# main.net
KiCad netlist of a schematic drawn in EAGLE
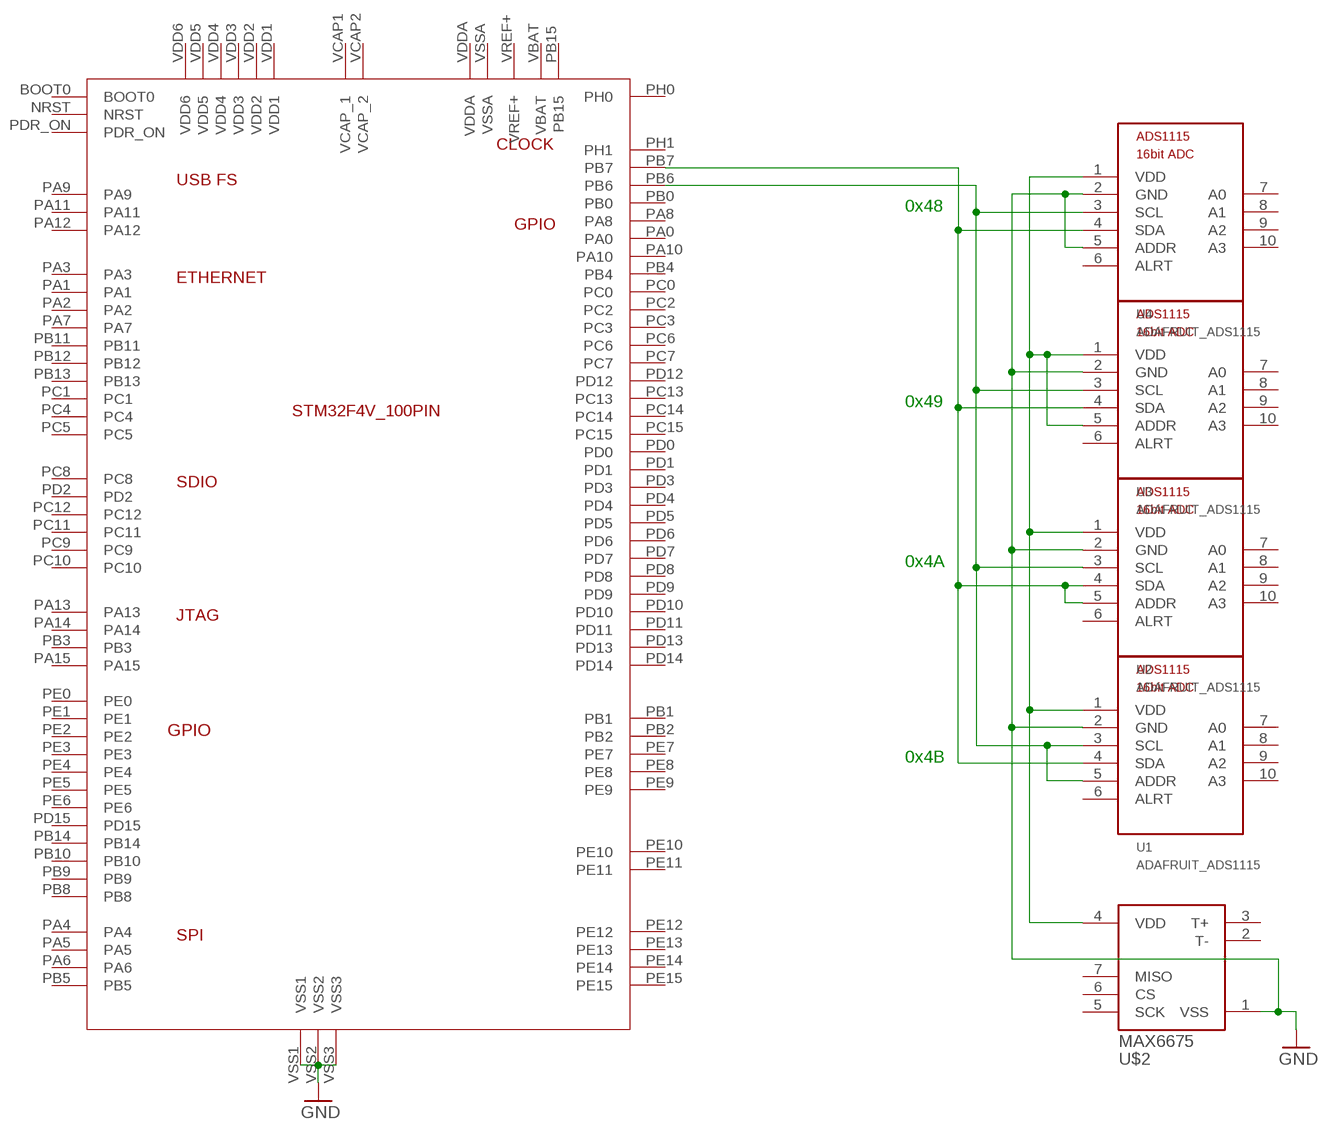
[diagram p0: schematic, sheet 1]

(export (version "E")
  (design (tool "Eeschema 10.0.6"))
  (components
    (comp (ref "U$1")
      (value "STM32F4V_100PIN_GPSBOARD")
      (footprint "eagle-import:LQFP100")
      (libsource (lib "eagle-import") (part "STM32F4V_100PIN_GPSBOARD"))
    )
    (comp (ref "U$2")
      (value "MAX6675")
      (footprint "eagle-import:SO08")
      (libsource (lib "eagle-import") (part "MAX6675"))
    )
    (comp (ref "U1")
      (value "ADAFRUIT_ADS1115")
      (footprint "eagle-import:ADAFRUIT_ADS1115_16BIT_I2C_ADC")
      (libsource (lib "eagle-import") (part "ADAFRUIT_ADS1115"))
    )
    (comp (ref "U2")
      (value "ADAFRUIT_ADS1115")
      (footprint "eagle-import:ADAFRUIT_ADS1115_16BIT_I2C_ADC")
      (libsource (lib "eagle-import") (part "ADAFRUIT_ADS1115"))
    )
    (comp (ref "U3")
      (value "ADAFRUIT_ADS1115")
      (footprint "eagle-import:ADAFRUIT_ADS1115_16BIT_I2C_ADC")
      (libsource (lib "eagle-import") (part "ADAFRUIT_ADS1115"))
    )
    (comp (ref "U4")
      (value "ADAFRUIT_ADS1115")
      (footprint "eagle-import:ADAFRUIT_ADS1115_16BIT_I2C_ADC")
      (libsource (lib "eagle-import") (part "ADAFRUIT_ADS1115"))
    )
  )
  (nets
    (net (code "1") (name "/VDD1") (class "Default")
      (node (ref "U$1") (pin "VDD1") (pinfunction "VDD1_VDD1") (pintype "power_in"))
    )
    (net (code "2") (name "/VDD2") (class "Default")
      (node (ref "U$1") (pin "VDD2") (pinfunction "VDD2_VDD2") (pintype "power_in"))
    )
    (net (code "3") (name "/VDD3") (class "Default")
      (node (ref "U$1") (pin "VDD3") (pinfunction "VDD3_VDD3") (pintype "power_in"))
    )
    (net (code "4") (name "/VDD4") (class "Default")
      (node (ref "U$1") (pin "VDD4") (pinfunction "VDD4_VDD4") (pintype "power_in"))
    )
    (net (code "5") (name "/VDD5") (class "Default")
      (node (ref "U$1") (pin "VDD5") (pinfunction "VDD5_VDD5") (pintype "power_in"))
    )
    (net (code "6") (name "/VDD6") (class "Default")
      (node (ref "U$1") (pin "VDD6") (pinfunction "VDD6_VDD6") (pintype "power_in"))
    )
    (net (code "7") (name "GND") (class "Default")
      (node (ref "U$1") (pin "VSS1") (pinfunction "VSS1_VSS1") (pintype "power_in"))
      (node (ref "U$1") (pin "VSS2") (pinfunction "VSS2_VSS2") (pintype "power_in"))
      (node (ref "U$1") (pin "VSS3") (pinfunction "VSS3_VSS3") (pintype "power_in"))
      (node (ref "U$2") (pin "1") (pinfunction "VSS_1") (pintype "bidirectional"))
      (node (ref "U1") (pin "2") (pinfunction "GND_2") (pintype "bidirectional"))
      (node (ref "U2") (pin "2") (pinfunction "GND_2") (pintype "bidirectional"))
      (node (ref "U3") (pin "2") (pinfunction "GND_2") (pintype "bidirectional"))
      (node (ref "U4") (pin "2") (pinfunction "GND_2") (pintype "bidirectional"))
      (node (ref "U4") (pin "5") (pinfunction "ADDR_5") (pintype "bidirectional"))
    )
    (net (code "8") (name "Net-(U$2-VDD)") (class "Default")
      (node (ref "U$2") (pin "4") (pinfunction "VDD_4") (pintype "bidirectional"))
      (node (ref "U1") (pin "1") (pinfunction "VDD_1") (pintype "bidirectional"))
      (node (ref "U2") (pin "1") (pinfunction "VDD_1") (pintype "bidirectional"))
      (node (ref "U3") (pin "1") (pinfunction "VDD_1") (pintype "bidirectional"))
      (node (ref "U3") (pin "5") (pinfunction "ADDR_5") (pintype "bidirectional"))
      (node (ref "U4") (pin "1") (pinfunction "VDD_1") (pintype "bidirectional"))
    )
    (net (code "9") (name "Net-(U1-ADDR)") (class "Default")
      (node (ref "U$1") (pin "PB6") (pinfunction "PB6_PB6") (pintype "bidirectional"))
      (node (ref "U1") (pin "3") (pinfunction "SCL_3") (pintype "bidirectional"))
      (node (ref "U1") (pin "5") (pinfunction "ADDR_5") (pintype "bidirectional"))
      (node (ref "U2") (pin "3") (pinfunction "SCL_3") (pintype "bidirectional"))
      (node (ref "U3") (pin "3") (pinfunction "SCL_3") (pintype "bidirectional"))
      (node (ref "U4") (pin "3") (pinfunction "SCL_3") (pintype "bidirectional"))
    )
    (net (code "10") (name "Net-(U1-SDA)") (class "Default")
      (node (ref "U$1") (pin "PB7") (pinfunction "PB7_PB7") (pintype "bidirectional"))
      (node (ref "U1") (pin "4") (pinfunction "SDA_4") (pintype "bidirectional"))
      (node (ref "U2") (pin "4") (pinfunction "SDA_4") (pintype "bidirectional"))
      (node (ref "U2") (pin "5") (pinfunction "ADDR_5") (pintype "bidirectional"))
      (node (ref "U3") (pin "4") (pinfunction "SDA_4") (pintype "bidirectional"))
      (node (ref "U4") (pin "4") (pinfunction "SDA_4") (pintype "bidirectional"))
    )
    (net (code "11") (name "unconnected-(U$1-PadBOOT0)") (class "Default")
      (node (ref "U$1") (pin "BOOT0") (pinfunction "BOOT0_BOOT0") (pintype "bidirectional"))
    )
    (net (code "12") (name "unconnected-(U$1-PadNRST)") (class "Default")
      (node (ref "U$1") (pin "NRST") (pinfunction "NRST_NRST") (pintype "bidirectional"))
    )
    (net (code "13") (name "unconnected-(U$1-PadPA0)") (class "Default")
      (node (ref "U$1") (pin "PA0") (pinfunction "PA0_PA0") (pintype "bidirectional"))
    )
    (net (code "14") (name "unconnected-(U$1-PadPA1)") (class "Default")
      (node (ref "U$1") (pin "PA1") (pinfunction "PA1_PA1") (pintype "bidirectional"))
    )
    (net (code "15") (name "unconnected-(U$1-PadPA2)") (class "Default")
      (node (ref "U$1") (pin "PA2") (pinfunction "PA2_PA2") (pintype "bidirectional"))
    )
    (net (code "16") (name "unconnected-(U$1-PadPA3)") (class "Default")
      (node (ref "U$1") (pin "PA3") (pinfunction "PA3_PA3") (pintype "bidirectional"))
    )
    (net (code "17") (name "unconnected-(U$1-PadPA4)") (class "Default")
      (node (ref "U$1") (pin "PA4") (pinfunction "PA4_PA4") (pintype "bidirectional"))
    )
    (net (code "18") (name "unconnected-(U$1-PadPA5)") (class "Default")
      (node (ref "U$1") (pin "PA5") (pinfunction "PA5_PA5") (pintype "bidirectional"))
    )
    (net (code "19") (name "unconnected-(U$1-PadPA6)") (class "Default")
      (node (ref "U$1") (pin "PA6") (pinfunction "PA6_PA6") (pintype "bidirectional"))
    )
    (net (code "20") (name "unconnected-(U$1-PadPA7)") (class "Default")
      (node (ref "U$1") (pin "PA7") (pinfunction "PA7_PA7") (pintype "bidirectional"))
    )
    (net (code "21") (name "unconnected-(U$1-PadPA8)") (class "Default")
      (node (ref "U$1") (pin "PA8") (pinfunction "PA8_PA8") (pintype "bidirectional"))
    )
    (net (code "22") (name "unconnected-(U$1-PadPA9)") (class "Default")
      (node (ref "U$1") (pin "PA9") (pinfunction "PA9_PA9") (pintype "bidirectional"))
    )
    (net (code "23") (name "unconnected-(U$1-PadPA10)") (class "Default")
      (node (ref "U$1") (pin "PA10") (pinfunction "PA10_PA10") (pintype "bidirectional"))
    )
    (net (code "24") (name "unconnected-(U$1-PadPA11)") (class "Default")
      (node (ref "U$1") (pin "PA11") (pinfunction "PA11_PA11") (pintype "bidirectional"))
    )
    (net (code "25") (name "unconnected-(U$1-PadPA12)") (class "Default")
      (node (ref "U$1") (pin "PA12") (pinfunction "PA12_PA12") (pintype "bidirectional"))
    )
    (net (code "26") (name "unconnected-(U$1-PadPA13)") (class "Default")
      (node (ref "U$1") (pin "PA13") (pinfunction "PA13_PA13") (pintype "bidirectional"))
    )
    (net (code "27") (name "unconnected-(U$1-PadPA14)") (class "Default")
      (node (ref "U$1") (pin "PA14") (pinfunction "PA14_PA14") (pintype "bidirectional"))
    )
    (net (code "28") (name "unconnected-(U$1-PadPA15)") (class "Default")
      (node (ref "U$1") (pin "PA15") (pinfunction "PA15_PA15") (pintype "bidirectional"))
    )
    (net (code "29") (name "unconnected-(U$1-PadPB0)") (class "Default")
      (node (ref "U$1") (pin "PB0") (pinfunction "PB0_PB0") (pintype "bidirectional"))
    )
    (net (code "30") (name "unconnected-(U$1-PadPB1)") (class "Default")
      (node (ref "U$1") (pin "PB1") (pinfunction "PB1_PB1") (pintype "bidirectional"))
    )
    (net (code "31") (name "unconnected-(U$1-PadPB2)") (class "Default")
      (node (ref "U$1") (pin "PB2") (pinfunction "PB2_PB2") (pintype "bidirectional"))
    )
    (net (code "32") (name "unconnected-(U$1-PadPB3)") (class "Default")
      (node (ref "U$1") (pin "PB3") (pinfunction "PB3_PB3") (pintype "bidirectional"))
    )
    (net (code "33") (name "unconnected-(U$1-PadPB4)") (class "Default")
      (node (ref "U$1") (pin "PB4") (pinfunction "PB4_PB4") (pintype "bidirectional"))
    )
    (net (code "34") (name "unconnected-(U$1-PadPB5)") (class "Default")
      (node (ref "U$1") (pin "PB5") (pinfunction "PB5_PB5") (pintype "bidirectional"))
    )
    (net (code "35") (name "unconnected-(U$1-PadPB8)") (class "Default")
      (node (ref "U$1") (pin "PB8") (pinfunction "PB8_PB8") (pintype "bidirectional"))
    )
    (net (code "36") (name "unconnected-(U$1-PadPB9)") (class "Default")
      (node (ref "U$1") (pin "PB9") (pinfunction "PB9_PB9") (pintype "bidirectional"))
    )
    (net (code "37") (name "unconnected-(U$1-PadPB10)") (class "Default")
      (node (ref "U$1") (pin "PB10") (pinfunction "PB10_PB10") (pintype "bidirectional"))
    )
    (net (code "38") (name "unconnected-(U$1-PadPB11)") (class "Default")
      (node (ref "U$1") (pin "PB11") (pinfunction "PB11_PB11") (pintype "bidirectional"))
    )
    (net (code "39") (name "unconnected-(U$1-PadPB12)") (class "Default")
      (node (ref "U$1") (pin "PB12") (pinfunction "PB12_PB12") (pintype "bidirectional"))
    )
    (net (code "40") (name "unconnected-(U$1-PadPB13)") (class "Default")
      (node (ref "U$1") (pin "PB13") (pinfunction "PB13_PB13") (pintype "bidirectional"))
    )
    (net (code "41") (name "unconnected-(U$1-PadPB14)") (class "Default")
      (node (ref "U$1") (pin "PB14") (pinfunction "PB14_PB14") (pintype "bidirectional"))
    )
    (net (code "42") (name "unconnected-(U$1-PadPB15)") (class "Default")
      (node (ref "U$1") (pin "PB15") (pinfunction "PB15_PB15") (pintype "bidirectional"))
    )
    (net (code "43") (name "unconnected-(U$1-PadPC0)") (class "Default")
      (node (ref "U$1") (pin "PC0") (pinfunction "PC0_PC0") (pintype "bidirectional"))
    )
    (net (code "44") (name "unconnected-(U$1-PadPC1)") (class "Default")
      (node (ref "U$1") (pin "PC1") (pinfunction "PC1_PC1") (pintype "bidirectional"))
    )
    (net (code "45") (name "unconnected-(U$1-PadPC2)") (class "Default")
      (node (ref "U$1") (pin "PC2") (pinfunction "PC2_PC2") (pintype "bidirectional"))
    )
    (net (code "46") (name "unconnected-(U$1-PadPC3)") (class "Default")
      (node (ref "U$1") (pin "PC3") (pinfunction "PC3_PC3") (pintype "bidirectional"))
    )
    (net (code "47") (name "unconnected-(U$1-PadPC4)") (class "Default")
      (node (ref "U$1") (pin "PC4") (pinfunction "PC4_PC4") (pintype "bidirectional"))
    )
    (net (code "48") (name "unconnected-(U$1-PadPC5)") (class "Default")
      (node (ref "U$1") (pin "PC5") (pinfunction "PC5_PC5") (pintype "bidirectional"))
    )
    (net (code "49") (name "unconnected-(U$1-PadPC6)") (class "Default")
      (node (ref "U$1") (pin "PC6") (pinfunction "PC6_PC6") (pintype "bidirectional"))
    )
    (net (code "50") (name "unconnected-(U$1-PadPC7)") (class "Default")
      (node (ref "U$1") (pin "PC7") (pinfunction "PC7_PC7") (pintype "bidirectional"))
    )
    (net (code "51") (name "unconnected-(U$1-PadPC8)") (class "Default")
      (node (ref "U$1") (pin "PC8") (pinfunction "PC8_PC8") (pintype "bidirectional"))
    )
    (net (code "52") (name "unconnected-(U$1-PadPC9)") (class "Default")
      (node (ref "U$1") (pin "PC9") (pinfunction "PC9_PC9") (pintype "bidirectional"))
    )
    (net (code "53") (name "unconnected-(U$1-PadPC10)") (class "Default")
      (node (ref "U$1") (pin "PC10") (pinfunction "PC10_PC10") (pintype "bidirectional"))
    )
    (net (code "54") (name "unconnected-(U$1-PadPC11)") (class "Default")
      (node (ref "U$1") (pin "PC11") (pinfunction "PC11_PC11") (pintype "bidirectional"))
    )
    (net (code "55") (name "unconnected-(U$1-PadPC12)") (class "Default")
      (node (ref "U$1") (pin "PC12") (pinfunction "PC12_PC12") (pintype "bidirectional"))
    )
    (net (code "56") (name "unconnected-(U$1-PadPC13)") (class "Default")
      (node (ref "U$1") (pin "PC13") (pinfunction "PC13_PC13") (pintype "bidirectional"))
    )
    (net (code "57") (name "unconnected-(U$1-PadPC14)") (class "Default")
      (node (ref "U$1") (pin "PC14") (pinfunction "PC14_PC14") (pintype "bidirectional"))
    )
    (net (code "58") (name "unconnected-(U$1-PadPC15)") (class "Default")
      (node (ref "U$1") (pin "PC15") (pinfunction "PC15_PC15") (pintype "bidirectional"))
    )
    (net (code "59") (name "unconnected-(U$1-PadPD0)") (class "Default")
      (node (ref "U$1") (pin "PD0") (pinfunction "PD0_PD0") (pintype "bidirectional"))
    )
    (net (code "60") (name "unconnected-(U$1-PadPD1)") (class "Default")
      (node (ref "U$1") (pin "PD1") (pinfunction "PD1_PD1") (pintype "bidirectional"))
    )
    (net (code "61") (name "unconnected-(U$1-PadPD2)") (class "Default")
      (node (ref "U$1") (pin "PD2") (pinfunction "PD2_PD2") (pintype "bidirectional"))
    )
    (net (code "62") (name "unconnected-(U$1-PadPD3)") (class "Default")
      (node (ref "U$1") (pin "PD3") (pinfunction "PD3_PD3") (pintype "bidirectional"))
    )
    (net (code "63") (name "unconnected-(U$1-PadPD4)") (class "Default")
      (node (ref "U$1") (pin "PD4") (pinfunction "PD4_PD4") (pintype "bidirectional"))
    )
    (net (code "64") (name "unconnected-(U$1-PadPD5)") (class "Default")
      (node (ref "U$1") (pin "PD5") (pinfunction "PD5_PD5") (pintype "bidirectional"))
    )
    (net (code "65") (name "unconnected-(U$1-PadPD6)") (class "Default")
      (node (ref "U$1") (pin "PD6") (pinfunction "PD6_PD6") (pintype "bidirectional"))
    )
    (net (code "66") (name "unconnected-(U$1-PadPD7)") (class "Default")
      (node (ref "U$1") (pin "PD7") (pinfunction "PD7_PD7") (pintype "bidirectional"))
    )
    (net (code "67") (name "unconnected-(U$1-PadPD8)") (class "Default")
      (node (ref "U$1") (pin "PD8") (pinfunction "PD8_PD8") (pintype "bidirectional"))
    )
    (net (code "68") (name "unconnected-(U$1-PadPD9)") (class "Default")
      (node (ref "U$1") (pin "PD9") (pinfunction "PD9_PD9") (pintype "bidirectional"))
    )
    (net (code "69") (name "unconnected-(U$1-PadPD10)") (class "Default")
      (node (ref "U$1") (pin "PD10") (pinfunction "PD10_PD10") (pintype "bidirectional"))
    )
    (net (code "70") (name "unconnected-(U$1-PadPD11)") (class "Default")
      (node (ref "U$1") (pin "PD11") (pinfunction "PD11_PD11") (pintype "bidirectional"))
    )
    (net (code "71") (name "unconnected-(U$1-PadPD12)") (class "Default")
      (node (ref "U$1") (pin "PD12") (pinfunction "PD12_PD12") (pintype "bidirectional"))
    )
    (net (code "72") (name "unconnected-(U$1-PadPD13)") (class "Default")
      (node (ref "U$1") (pin "PD13") (pinfunction "PD13_PD13") (pintype "bidirectional"))
    )
    (net (code "73") (name "unconnected-(U$1-PadPD14)") (class "Default")
      (node (ref "U$1") (pin "PD14") (pinfunction "PD14_PD14") (pintype "bidirectional"))
    )
    (net (code "74") (name "unconnected-(U$1-PadPD15)") (class "Default")
      (node (ref "U$1") (pin "PD15") (pinfunction "PD15_PD15") (pintype "bidirectional"))
    )
    (net (code "75") (name "unconnected-(U$1-PadPDR_ON)") (class "Default")
      (node (ref "U$1") (pin "PDR_ON") (pinfunction "PDR_ON_PDR_ON") (pintype "bidirectional"))
    )
    (net (code "76") (name "unconnected-(U$1-PadPE0)") (class "Default")
      (node (ref "U$1") (pin "PE0") (pinfunction "PE0_PE0") (pintype "bidirectional"))
    )
    (net (code "77") (name "unconnected-(U$1-PadPE1)") (class "Default")
      (node (ref "U$1") (pin "PE1") (pinfunction "PE1_PE1") (pintype "bidirectional"))
    )
    (net (code "78") (name "unconnected-(U$1-PadPE2)") (class "Default")
      (node (ref "U$1") (pin "PE2") (pinfunction "PE2_PE2") (pintype "bidirectional"))
    )
    (net (code "79") (name "unconnected-(U$1-PadPE3)") (class "Default")
      (node (ref "U$1") (pin "PE3") (pinfunction "PE3_PE3") (pintype "bidirectional"))
    )
    (net (code "80") (name "unconnected-(U$1-PadPE4)") (class "Default")
      (node (ref "U$1") (pin "PE4") (pinfunction "PE4_PE4") (pintype "bidirectional"))
    )
    (net (code "81") (name "unconnected-(U$1-PadPE5)") (class "Default")
      (node (ref "U$1") (pin "PE5") (pinfunction "PE5_PE5") (pintype "bidirectional"))
    )
    (net (code "82") (name "unconnected-(U$1-PadPE6)") (class "Default")
      (node (ref "U$1") (pin "PE6") (pinfunction "PE6_PE6") (pintype "bidirectional"))
    )
    (net (code "83") (name "unconnected-(U$1-PadPE7)") (class "Default")
      (node (ref "U$1") (pin "PE7") (pinfunction "PE7_PE7") (pintype "bidirectional"))
    )
    (net (code "84") (name "unconnected-(U$1-PadPE8)") (class "Default")
      (node (ref "U$1") (pin "PE8") (pinfunction "PE8_PE8") (pintype "bidirectional"))
    )
    (net (code "85") (name "unconnected-(U$1-PadPE9)") (class "Default")
      (node (ref "U$1") (pin "PE9") (pinfunction "PE9_PE9") (pintype "bidirectional"))
    )
    (net (code "86") (name "unconnected-(U$1-PadPE10)") (class "Default")
      (node (ref "U$1") (pin "PE10") (pinfunction "PE10_PE10") (pintype "bidirectional"))
    )
    (net (code "87") (name "unconnected-(U$1-PadPE11)") (class "Default")
      (node (ref "U$1") (pin "PE11") (pinfunction "PE11_PE11") (pintype "bidirectional"))
    )
    (net (code "88") (name "unconnected-(U$1-PadPE12)") (class "Default")
      (node (ref "U$1") (pin "PE12") (pinfunction "PE12_PE12") (pintype "bidirectional"))
    )
    (net (code "89") (name "unconnected-(U$1-PadPE13)") (class "Default")
      (node (ref "U$1") (pin "PE13") (pinfunction "PE13_PE13") (pintype "bidirectional"))
    )
    (net (code "90") (name "unconnected-(U$1-PadPE14)") (class "Default")
      (node (ref "U$1") (pin "PE14") (pinfunction "PE14_PE14") (pintype "bidirectional"))
    )
    (net (code "91") (name "unconnected-(U$1-PadPE15)") (class "Default")
      (node (ref "U$1") (pin "PE15") (pinfunction "PE15_PE15") (pintype "bidirectional"))
    )
    (net (code "92") (name "unconnected-(U$1-PadPH0)") (class "Default")
      (node (ref "U$1") (pin "PH0") (pinfunction "PH0_PH0") (pintype "bidirectional"))
    )
    (net (code "93") (name "unconnected-(U$1-PadPH1)") (class "Default")
      (node (ref "U$1") (pin "PH1") (pinfunction "PH1_PH1") (pintype "bidirectional"))
    )
    (net (code "94") (name "unconnected-(U$1-PadVBAT)") (class "Default")
      (node (ref "U$1") (pin "VBAT") (pinfunction "VBAT_VBAT") (pintype "bidirectional"))
    )
    (net (code "95") (name "unconnected-(U$1-PadVDDA)") (class "Default")
      (node (ref "U$1") (pin "VDDA") (pinfunction "VDDA_VDDA") (pintype "bidirectional"))
    )
    (net (code "96") (name "unconnected-(U$1-PadVREF+)") (class "Default")
      (node (ref "U$1") (pin "VREF+") (pinfunction "VREF+_VREF+") (pintype "bidirectional"))
    )
    (net (code "97") (name "unconnected-(U$1-PadVSSA)") (class "Default")
      (node (ref "U$1") (pin "VSSA") (pinfunction "VSSA_VSSA") (pintype "bidirectional"))
    )
    (net (code "98") (name "unconnected-(U$1-VCAP_1-PadVCAP1)") (class "Default")
      (node (ref "U$1") (pin "VCAP1") (pinfunction "VCAP_1_VCAP1") (pintype "bidirectional"))
    )
    (net (code "99") (name "unconnected-(U$1-VCAP_2-PadVCAP2)") (class "Default")
      (node (ref "U$1") (pin "VCAP2") (pinfunction "VCAP_2_VCAP2") (pintype "bidirectional"))
    )
    (net (code "100") (name "unconnected-(U$2-CS-Pad6)") (class "Default")
      (node (ref "U$2") (pin "6") (pinfunction "CS_6") (pintype "bidirectional"))
    )
    (net (code "101") (name "unconnected-(U$2-MISO-Pad7)") (class "Default")
      (node (ref "U$2") (pin "7") (pinfunction "MISO_7") (pintype "bidirectional"))
    )
    (net (code "102") (name "unconnected-(U$2-SCK-Pad5)") (class "Default")
      (node (ref "U$2") (pin "5") (pinfunction "SCK_5") (pintype "bidirectional"))
    )
    (net (code "103") (name "unconnected-(U$2-T+-Pad3)") (class "Default")
      (node (ref "U$2") (pin "3") (pinfunction "T+_3") (pintype "bidirectional"))
    )
    (net (code "104") (name "unconnected-(U$2-T--Pad2)") (class "Default")
      (node (ref "U$2") (pin "2") (pinfunction "T-_2") (pintype "bidirectional"))
    )
    (net (code "105") (name "unconnected-(U1-A0-Pad7)") (class "Default")
      (node (ref "U1") (pin "7") (pinfunction "A0_7") (pintype "bidirectional"))
    )
    (net (code "106") (name "unconnected-(U1-A1-Pad8)") (class "Default")
      (node (ref "U1") (pin "8") (pinfunction "A1_8") (pintype "bidirectional"))
    )
    (net (code "107") (name "unconnected-(U1-A2-Pad9)") (class "Default")
      (node (ref "U1") (pin "9") (pinfunction "A2_9") (pintype "bidirectional"))
    )
    (net (code "108") (name "unconnected-(U1-A3-Pad10)") (class "Default")
      (node (ref "U1") (pin "10") (pinfunction "A3_10") (pintype "bidirectional"))
    )
    (net (code "109") (name "unconnected-(U1-ALRT-Pad6)") (class "Default")
      (node (ref "U1") (pin "6") (pinfunction "ALRT_6") (pintype "bidirectional"))
    )
    (net (code "110") (name "unconnected-(U2-A0-Pad7)") (class "Default")
      (node (ref "U2") (pin "7") (pinfunction "A0_7") (pintype "bidirectional"))
    )
    (net (code "111") (name "unconnected-(U2-A1-Pad8)") (class "Default")
      (node (ref "U2") (pin "8") (pinfunction "A1_8") (pintype "bidirectional"))
    )
    (net (code "112") (name "unconnected-(U2-A2-Pad9)") (class "Default")
      (node (ref "U2") (pin "9") (pinfunction "A2_9") (pintype "bidirectional"))
    )
    (net (code "113") (name "unconnected-(U2-A3-Pad10)") (class "Default")
      (node (ref "U2") (pin "10") (pinfunction "A3_10") (pintype "bidirectional"))
    )
    (net (code "114") (name "unconnected-(U2-ALRT-Pad6)") (class "Default")
      (node (ref "U2") (pin "6") (pinfunction "ALRT_6") (pintype "bidirectional"))
    )
    (net (code "115") (name "unconnected-(U3-A0-Pad7)") (class "Default")
      (node (ref "U3") (pin "7") (pinfunction "A0_7") (pintype "bidirectional"))
    )
    (net (code "116") (name "unconnected-(U3-A1-Pad8)") (class "Default")
      (node (ref "U3") (pin "8") (pinfunction "A1_8") (pintype "bidirectional"))
    )
    (net (code "117") (name "unconnected-(U3-A2-Pad9)") (class "Default")
      (node (ref "U3") (pin "9") (pinfunction "A2_9") (pintype "bidirectional"))
    )
    (net (code "118") (name "unconnected-(U3-A3-Pad10)") (class "Default")
      (node (ref "U3") (pin "10") (pinfunction "A3_10") (pintype "bidirectional"))
    )
    (net (code "119") (name "unconnected-(U3-ALRT-Pad6)") (class "Default")
      (node (ref "U3") (pin "6") (pinfunction "ALRT_6") (pintype "bidirectional"))
    )
    (net (code "120") (name "unconnected-(U4-A0-Pad7)") (class "Default")
      (node (ref "U4") (pin "7") (pinfunction "A0_7") (pintype "bidirectional"))
    )
    (net (code "121") (name "unconnected-(U4-A1-Pad8)") (class "Default")
      (node (ref "U4") (pin "8") (pinfunction "A1_8") (pintype "bidirectional"))
    )
    (net (code "122") (name "unconnected-(U4-A2-Pad9)") (class "Default")
      (node (ref "U4") (pin "9") (pinfunction "A2_9") (pintype "bidirectional"))
    )
    (net (code "123") (name "unconnected-(U4-A3-Pad10)") (class "Default")
      (node (ref "U4") (pin "10") (pinfunction "A3_10") (pintype "bidirectional"))
    )
    (net (code "124") (name "unconnected-(U4-ALRT-Pad6)") (class "Default")
      (node (ref "U4") (pin "6") (pinfunction "ALRT_6") (pintype "bidirectional"))
    )
  )
)
